# Lighting.net
KiCad netlist of a schematic drawn in Altium Designer
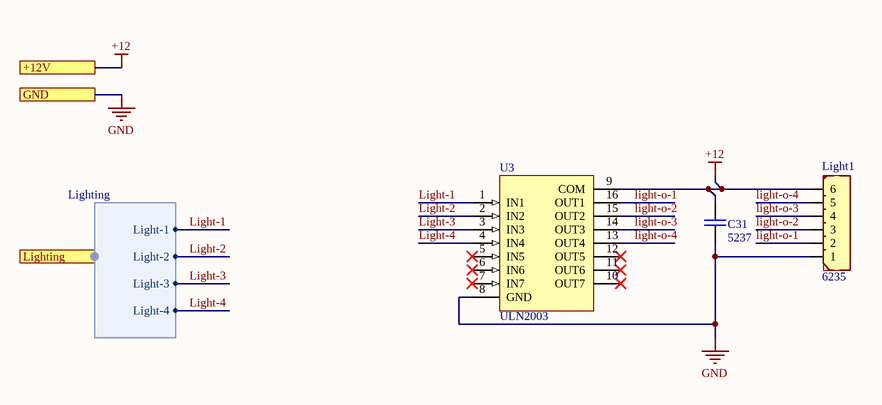
[diagram p0: Lighting.SchDoc]

(export (version "E")
  (design (tool "Eeschema 10.0.6"))
  (components
    (comp (ref "C31")
      (value "1u'F, 50'V")
      (footprint "CAP 1206/3216")
      (description "Bipolar ceramic capacitor SMD")
      (fields (field (name "INFLOW") "5237") (field (name "VALIDATION") "Valid"))
      (libsource (lib "aKaReZa") (part "Cap_Multi_1u_50_1206"))
    )
    (comp (ref "Light1")
      (value "6'Pin")
      (footprint "645006114822")
      (description "6'Pin Power Connector")
      (fields (field (name "INFLOW") "6235") (field (name "VALIDATION") "Valid"))
      (libsource (lib "aKaReZa") (part "Con_Power_6_PC_V"))
    )
    (comp (ref "U3")
      (value "ULN2003")
      (footprint "SO16_M")
      (description "Seven darlington array drivers")
      (fields (field (name "VALIDATION") "Valid"))
      (libsource (lib "vending-pad-002") (part "IC_Driver_ULN2003"))
    )
  )
  (nets
    (net (code "2") (name "+12") (class "Default")
      (node (ref "C31") (pin "2") (pinfunction "2_2") (pintype "passive"))
      (node (ref "Light1") (pin "6") (pinfunction "6_6") (pintype "passive"))
      (node (ref "U3") (pin "9") (pinfunction "COM_9") (pintype "passive"))
    )
    (net (code "3") (name "/Light-1") (class "Default")
      (node (ref "U3") (pin "1") (pinfunction "IN1_1") (pintype "input"))
    )
    (net (code "4") (name "/Light-2") (class "Default")
      (node (ref "U3") (pin "2") (pinfunction "IN2_2") (pintype "input"))
    )
    (net (code "5") (name "/Light-3") (class "Default")
      (node (ref "U3") (pin "3") (pinfunction "IN3_3") (pintype "input"))
    )
    (net (code "6") (name "/Light-4") (class "Default")
      (node (ref "U3") (pin "4") (pinfunction "IN4_4") (pintype "input"))
    )
    (net (code "7") (name "/light-o-1") (class "Default")
      (node (ref "Light1") (pin "2") (pinfunction "2_2") (pintype "passive"))
      (node (ref "U3") (pin "16") (pinfunction "OUT1_16") (pintype "open_collector"))
    )
    (net (code "8") (name "/light-o-2") (class "Default")
      (node (ref "Light1") (pin "3") (pinfunction "3_3") (pintype "passive"))
      (node (ref "U3") (pin "15") (pinfunction "OUT2_15") (pintype "open_collector"))
    )
    (net (code "9") (name "/light-o-3") (class "Default")
      (node (ref "Light1") (pin "4") (pinfunction "4_4") (pintype "passive"))
      (node (ref "U3") (pin "14") (pinfunction "OUT3_14") (pintype "open_collector"))
    )
    (net (code "10") (name "/light-o-4") (class "Default")
      (node (ref "Light1") (pin "5") (pinfunction "5_5") (pintype "passive"))
      (node (ref "U3") (pin "13") (pinfunction "OUT4_13") (pintype "open_collector"))
    )
    (net (code "12") (name "GND") (class "Default")
      (node (ref "C31") (pin "1") (pinfunction "1_1") (pintype "passive"))
      (node (ref "Light1") (pin "1") (pinfunction "1_1") (pintype "passive"))
      (node (ref "U3") (pin "8") (pinfunction "GND_8") (pintype "power_in"))
    )
    (net (code "13") (name "unconnected-(U3-IN5-Pad5)") (class "Default")
      (node (ref "U3") (pin "5") (pinfunction "IN5_5") (pintype "input+no_connect"))
    )
    (net (code "14") (name "unconnected-(U3-IN6-Pad6)") (class "Default")
      (node (ref "U3") (pin "6") (pinfunction "IN6_6") (pintype "input+no_connect"))
    )
    (net (code "15") (name "unconnected-(U3-IN7-Pad7)") (class "Default")
      (node (ref "U3") (pin "7") (pinfunction "IN7_7") (pintype "input+no_connect"))
    )
    (net (code "16") (name "unconnected-(U3-OUT5-Pad12)") (class "Default")
      (node (ref "U3") (pin "12") (pinfunction "OUT5_12") (pintype "open_collector+no_connect"))
    )
    (net (code "17") (name "unconnected-(U3-OUT6-Pad11)") (class "Default")
      (node (ref "U3") (pin "11") (pinfunction "OUT6_11") (pintype "open_collector+no_connect"))
    )
    (net (code "18") (name "unconnected-(U3-OUT7-Pad10)") (class "Default")
      (node (ref "U3") (pin "10") (pinfunction "OUT7_10") (pintype "open_collector+no_connect"))
    )
  )
)
